# RelaysBoard.net
KiCad netlist of a schematic drawn in EAGLE
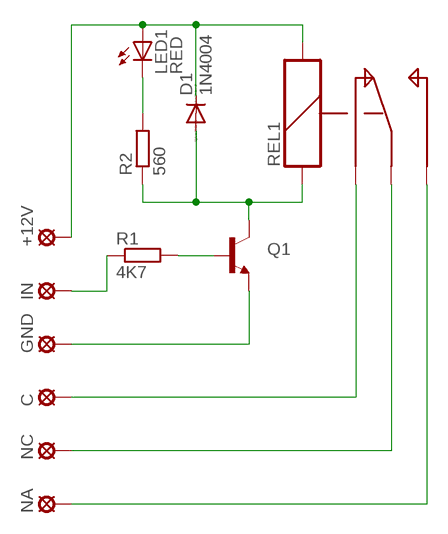
[diagram p0: schematic, sheet 1]

(export (version "E")
  (design (tool "Eeschema 10.0.6"))
  (components
    (comp (ref "+12V")
      (value "LSP10")
      (footprint "eagle-import:LSP10")
      (libsource (lib "eagle-import") (part "LSP10"))
    )
    (comp (ref "C")
      (value "LSP10")
      (footprint "eagle-import:LSP10")
      (libsource (lib "eagle-import") (part "LSP10"))
    )
    (comp (ref "D1")
      (value "1N4004")
      (footprint "eagle-import:DO41-10")
      (libsource (lib "eagle-import") (part "1N4004"))
    )
    (comp (ref "GND")
      (value "LSP10")
      (footprint "eagle-import:LSP10")
      (libsource (lib "eagle-import") (part "LSP10"))
    )
    (comp (ref "IN")
      (value "LSP10")
      (footprint "eagle-import:LSP10")
      (libsource (lib "eagle-import") (part "LSP10"))
    )
    (comp (ref "LED1")
      (value "RED")
      (footprint "eagle-import:LED5MM")
      (libsource (lib "eagle-import") (part "LED5MM"))
    )
    (comp (ref "NA")
      (value "LSP10")
      (footprint "eagle-import:LSP10")
      (libsource (lib "eagle-import") (part "LSP10"))
    )
    (comp (ref "NC")
      (value "LSP10")
      (footprint "eagle-import:LSP10")
      (libsource (lib "eagle-import") (part "LSP10"))
    )
    (comp (ref "Q1")
      (value "TRANSISTOR_NPNBC547")
      (footprint "eagle-import:TO-92-AMMO")
      (libsource (lib "eagle-import") (part "TRANSISTOR_NPNBC547"))
    )
    (comp (ref "R1")
      (value "4K7")
      (footprint "eagle-import:0207_12")
      (libsource (lib "eagle-import") (part "R-EU_0207/12"))
    )
    (comp (ref "R2")
      (value "560")
      (footprint "eagle-import:0207_10")
      (libsource (lib "eagle-import") (part "resistor_R-EU_0207/10"))
    )
    (comp (ref "REL1")
      (value "REL-5PIN")
      (footprint "eagle-import:REL-5PIN")
      (libsource (lib "eagle-import") (part "REL-5PIN"))
    )
  )
  (nets
    (net (code "1") (name "Net-(+12V-PadMP)") (class "Default")
      (node (ref "+12V") (pin "MP") (pinfunction "MP_MP") (pintype "passive"))
      (node (ref "D1") (pin "C") (pinfunction "C_C") (pintype "passive"))
      (node (ref "LED1") (pin "A") (pinfunction "A_A") (pintype "passive"))
      (node (ref "REL1") (pin "S2") (pinfunction "S2_S2") (pintype "passive"))
    )
    (net (code "2") (name "Net-(C-PadMP)") (class "Default")
      (node (ref "C") (pin "MP") (pinfunction "MP_MP") (pintype "passive"))
      (node (ref "REL1") (pin "S") (pinfunction "S_S") (pintype "passive"))
    )
    (net (code "3") (name "Net-(IN-PadMP)") (class "Default")
      (node (ref "IN") (pin "MP") (pinfunction "MP_MP") (pintype "passive"))
      (node (ref "R1") (pin "1") (pinfunction "1_1") (pintype "passive"))
    )
    (net (code "4") (name "Net-(LED1-C)") (class "Default")
      (node (ref "LED1") (pin "K") (pinfunction "C_K") (pintype "passive"))
      (node (ref "R2") (pin "2") (pinfunction "2_2") (pintype "passive"))
    )
    (net (code "5") (name "Net-(NA-PadMP)") (class "Default")
      (node (ref "NA") (pin "MP") (pinfunction "MP_MP") (pintype "passive"))
      (node (ref "REL1") (pin "O") (pinfunction "O_O") (pintype "passive"))
    )
    (net (code "6") (name "Net-(NC-PadMP)") (class "Default")
      (node (ref "NC") (pin "MP") (pinfunction "MP_MP") (pintype "passive"))
      (node (ref "REL1") (pin "C") (pinfunction "C_C") (pintype "passive"))
    )
    (net (code "7") (name "Net-(Q1-B)") (class "Default")
      (node (ref "Q1") (pin "2") (pinfunction "B_2") (pintype "passive"))
      (node (ref "R1") (pin "2") (pinfunction "2_2") (pintype "passive"))
    )
    (net (code "8") (name "Net-(Q1-C)") (class "Default")
      (node (ref "D1") (pin "A") (pinfunction "A_A") (pintype "passive"))
      (node (ref "Q1") (pin "1") (pinfunction "C_1") (pintype "passive"))
      (node (ref "R2") (pin "1") (pinfunction "1_1") (pintype "passive"))
      (node (ref "REL1") (pin "S1") (pinfunction "S1_S1") (pintype "passive"))
    )
    (net (code "9") (name "Net-(Q1-E)") (class "Default")
      (node (ref "GND") (pin "MP") (pinfunction "MP_MP") (pintype "passive"))
      (node (ref "Q1") (pin "3") (pinfunction "E_3") (pintype "passive"))
    )
  )
)
